# BrazoRobotico.net
KiCad netlist of a schematic drawn in EAGLE
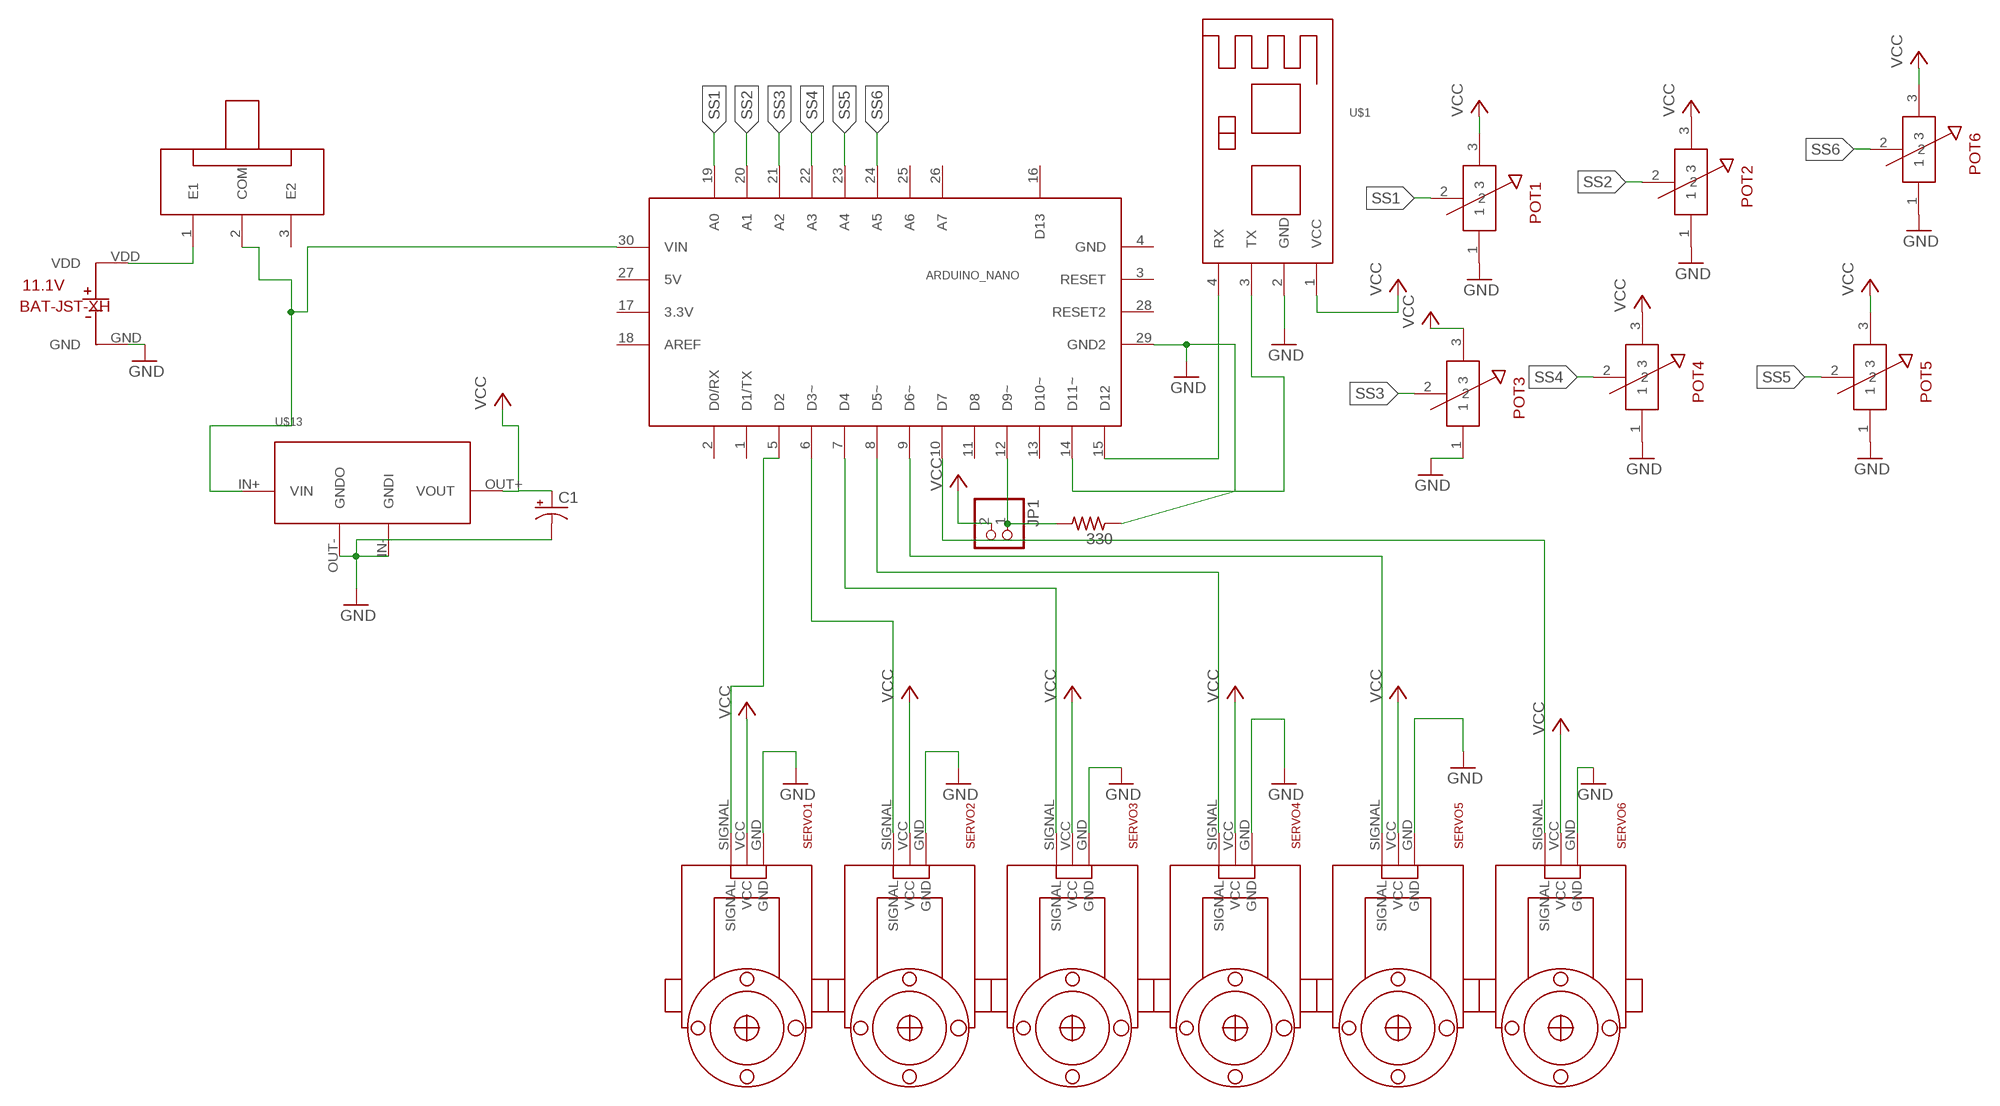
[diagram p0: schematic, sheet 1]

(export (version "E")
  (design (tool "Eeschema 10.0.6"))
  (components
    (comp (ref "11.1V")
      (value "BAT-JST-XH")
      (footprint "eagle-import:JST-XH-2")
      (libsource (lib "eagle-import") (part "BAT-JST-XH"))
    )
    (comp (ref "330")
      (value "R-US_0207/7")
      (footprint "eagle-import:0207_7")
      (libsource (lib "eagle-import") (part "R-US_0207/7"))
    )
    (comp (ref "ARDUINO_NANO")
      (value "NANO")
      (footprint "eagle-import:NANO")
      (libsource (lib "eagle-import") (part "NANO"))
    )
    (comp (ref "C1")
      (value "CPOL-USE5-10.5")
      (footprint "eagle-import:E5-10,5")
      (libsource (lib "eagle-import") (part "CPOL-USE5-10.5"))
    )
    (comp (ref "JP1")
      (value "PINHD-1X2")
      (footprint "eagle-import:1X02")
      (libsource (lib "eagle-import") (part "PINHD-1X2"))
    )
    (comp (ref "POT1")
      (value "POTENCIOMETRO_GDE")
      (footprint "eagle-import:POTENCIOMETRO_GENERICO")
      (libsource (lib "eagle-import") (part "POTENCIOMETRO_GDE"))
    )
    (comp (ref "POT2")
      (value "POTENCIOMETRO_GDE")
      (footprint "eagle-import:POTENCIOMETRO_GENERICO")
      (libsource (lib "eagle-import") (part "POTENCIOMETRO_GDE"))
    )
    (comp (ref "POT3")
      (value "POTENCIOMETRO_GDE")
      (footprint "eagle-import:POTENCIOMETRO_GENERICO")
      (libsource (lib "eagle-import") (part "POTENCIOMETRO_GDE"))
    )
    (comp (ref "POT4")
      (value "POTENCIOMETRO_GDE")
      (footprint "eagle-import:POTENCIOMETRO_GENERICO")
      (libsource (lib "eagle-import") (part "POTENCIOMETRO_GDE"))
    )
    (comp (ref "POT5")
      (value "POTENCIOMETRO_GDE")
      (footprint "eagle-import:POTENCIOMETRO_GENERICO")
      (libsource (lib "eagle-import") (part "POTENCIOMETRO_GDE"))
    )
    (comp (ref "POT6")
      (value "POTENCIOMETRO_GDE")
      (footprint "eagle-import:POTENCIOMETRO_GENERICO")
      (libsource (lib "eagle-import") (part "POTENCIOMETRO_GDE"))
    )
    (comp (ref "SERVO1")
      (value "SERVOMOTORES")
      (footprint "eagle-import:SERVO")
      (libsource (lib "eagle-import") (part "SERVOMOTORES"))
    )
    (comp (ref "SERVO2")
      (value "SERVOMOTORES")
      (footprint "eagle-import:SERVO")
      (libsource (lib "eagle-import") (part "SERVOMOTORES"))
    )
    (comp (ref "SERVO3")
      (value "SERVOMOTORES")
      (footprint "eagle-import:SERVO")
      (libsource (lib "eagle-import") (part "SERVOMOTORES"))
    )
    (comp (ref "SERVO4")
      (value "SERVOMOTORES")
      (footprint "eagle-import:SERVO")
      (libsource (lib "eagle-import") (part "SERVOMOTORES"))
    )
    (comp (ref "SERVO5")
      (value "SERVOMOTORES")
      (footprint "eagle-import:SERVO")
      (libsource (lib "eagle-import") (part "SERVOMOTORES"))
    )
    (comp (ref "SERVO6")
      (value "SERVOMOTORES")
      (footprint "eagle-import:SERVO")
      (libsource (lib "eagle-import") (part "SERVOMOTORES"))
    )
    (comp (ref "U$1")
      (value "HC-06")
      (footprint "eagle-import:HC-06")
      (libsource (lib "eagle-import") (part "HC-06"))
    )
    (comp (ref "U$13")
      (value "STEPDOWN")
      (footprint "eagle-import:STEPDOWN")
      (libsource (lib "eagle-import") (part "STEPDOWN"))
    )
    (comp (ref "U$14")
      (value "TRIPLEPOLO")
      (footprint "eagle-import:TRIPLEPOLO")
      (libsource (lib "eagle-import") (part "TRIPLEPOLO"))
    )
  )
  (nets
    (net (code "1") (name "GND") (class "Default")
      (node (ref "11.1V") (pin "GND") (pinfunction "GND_GND") (pintype "bidirectional"))
      (node (ref "330") (pin "1") (pinfunction "1_1") (pintype "passive"))
      (node (ref "ARDUINO_NANO") (pin "29") (pinfunction "GND2_29") (pintype "bidirectional"))
      (node (ref "C1") (pin "-") (pinfunction "-_-") (pintype "passive"))
      (node (ref "POT1") (pin "1") (pinfunction "1_1") (pintype "bidirectional"))
      (node (ref "POT2") (pin "1") (pinfunction "1_1") (pintype "bidirectional"))
      (node (ref "POT3") (pin "1") (pinfunction "1_1") (pintype "bidirectional"))
      (node (ref "POT4") (pin "1") (pinfunction "1_1") (pintype "bidirectional"))
      (node (ref "POT5") (pin "1") (pinfunction "1_1") (pintype "bidirectional"))
      (node (ref "POT6") (pin "1") (pinfunction "1_1") (pintype "bidirectional"))
      (node (ref "SERVO1") (pin "GND") (pinfunction "GND_GND") (pintype "bidirectional"))
      (node (ref "SERVO2") (pin "GND") (pinfunction "GND_GND") (pintype "bidirectional"))
      (node (ref "SERVO3") (pin "GND") (pinfunction "GND_GND") (pintype "bidirectional"))
      (node (ref "SERVO4") (pin "GND") (pinfunction "GND_GND") (pintype "bidirectional"))
      (node (ref "SERVO5") (pin "GND") (pinfunction "GND_GND") (pintype "bidirectional"))
      (node (ref "SERVO6") (pin "GND") (pinfunction "GND_GND") (pintype "bidirectional"))
      (node (ref "U$1") (pin "2") (pinfunction "GND_2") (pintype "bidirectional"))
      (node (ref "U$13") (pin "IN-") (pinfunction "GNDI_IN-") (pintype "bidirectional"))
      (node (ref "U$13") (pin "OUT-") (pinfunction "GNDO_OUT-") (pintype "bidirectional"))
    )
    (net (code "2") (name "Net-(ARDUINO_NANO-D2)") (class "Default")
      (node (ref "ARDUINO_NANO") (pin "5") (pinfunction "D2_5") (pintype "bidirectional"))
      (node (ref "SERVO1") (pin "SIGNAL") (pinfunction "SIGNAL_SIGNAL") (pintype "bidirectional"))
    )
    (net (code "3") (name "Net-(ARDUINO_NANO-D3~{})") (class "Default")
      (node (ref "ARDUINO_NANO") (pin "6") (pinfunction "D3~{}_6") (pintype "bidirectional"))
      (node (ref "SERVO2") (pin "SIGNAL") (pinfunction "SIGNAL_SIGNAL") (pintype "bidirectional"))
    )
    (net (code "4") (name "Net-(ARDUINO_NANO-D4)") (class "Default")
      (node (ref "ARDUINO_NANO") (pin "7") (pinfunction "D4_7") (pintype "bidirectional"))
      (node (ref "SERVO3") (pin "SIGNAL") (pinfunction "SIGNAL_SIGNAL") (pintype "bidirectional"))
    )
    (net (code "5") (name "Net-(ARDUINO_NANO-D5~{})") (class "Default")
      (node (ref "ARDUINO_NANO") (pin "8") (pinfunction "D5~{}_8") (pintype "bidirectional"))
      (node (ref "SERVO4") (pin "SIGNAL") (pinfunction "SIGNAL_SIGNAL") (pintype "bidirectional"))
    )
    (net (code "6") (name "Net-(ARDUINO_NANO-D6~{})") (class "Default")
      (node (ref "ARDUINO_NANO") (pin "9") (pinfunction "D6~{}_9") (pintype "bidirectional"))
      (node (ref "SERVO5") (pin "SIGNAL") (pinfunction "SIGNAL_SIGNAL") (pintype "bidirectional"))
    )
    (net (code "7") (name "Net-(ARDUINO_NANO-D7)") (class "Default")
      (node (ref "ARDUINO_NANO") (pin "10") (pinfunction "D7_10") (pintype "bidirectional"))
      (node (ref "SERVO6") (pin "SIGNAL") (pinfunction "SIGNAL_SIGNAL") (pintype "bidirectional"))
    )
    (net (code "8") (name "Net-(ARDUINO_NANO-D9~{})") (class "Default")
      (node (ref "330") (pin "2") (pinfunction "2_2") (pintype "passive"))
      (node (ref "ARDUINO_NANO") (pin "12") (pinfunction "D9~{}_12") (pintype "bidirectional"))
      (node (ref "JP1") (pin "1") (pinfunction "1_1") (pintype "passive"))
    )
    (net (code "9") (name "Net-(ARDUINO_NANO-D11~{})") (class "Default")
      (node (ref "ARDUINO_NANO") (pin "14") (pinfunction "D11~{}_14") (pintype "bidirectional"))
      (node (ref "U$1") (pin "3") (pinfunction "TX_3") (pintype "bidirectional"))
    )
    (net (code "10") (name "Net-(ARDUINO_NANO-D12)") (class "Default")
      (node (ref "ARDUINO_NANO") (pin "15") (pinfunction "D12_15") (pintype "bidirectional"))
      (node (ref "U$1") (pin "4") (pinfunction "RX_4") (pintype "bidirectional"))
    )
    (net (code "11") (name "Net-(ARDUINO_NANO-VIN)") (class "Default")
      (node (ref "ARDUINO_NANO") (pin "30") (pinfunction "VIN_30") (pintype "bidirectional"))
      (node (ref "U$13") (pin "IN+") (pinfunction "VIN_IN+") (pintype "bidirectional"))
      (node (ref "U$14") (pin "2") (pinfunction "COM_2") (pintype "bidirectional"))
    )
    (net (code "12") (name "Net-(U$14-E1)") (class "Default")
      (node (ref "11.1V") (pin "VDD") (pinfunction "VDD_VDD") (pintype "bidirectional"))
      (node (ref "U$14") (pin "1") (pinfunction "E1_1") (pintype "bidirectional"))
    )
    (net (code "13") (name "SS1") (class "Default")
      (node (ref "ARDUINO_NANO") (pin "19") (pinfunction "A0_19") (pintype "bidirectional"))
      (node (ref "POT1") (pin "2") (pinfunction "2_2") (pintype "bidirectional"))
    )
    (net (code "14") (name "SS2") (class "Default")
      (node (ref "ARDUINO_NANO") (pin "20") (pinfunction "A1_20") (pintype "bidirectional"))
      (node (ref "POT2") (pin "2") (pinfunction "2_2") (pintype "bidirectional"))
    )
    (net (code "15") (name "SS3") (class "Default")
      (node (ref "ARDUINO_NANO") (pin "21") (pinfunction "A2_21") (pintype "bidirectional"))
      (node (ref "POT3") (pin "2") (pinfunction "2_2") (pintype "bidirectional"))
    )
    (net (code "16") (name "SS4") (class "Default")
      (node (ref "ARDUINO_NANO") (pin "22") (pinfunction "A3_22") (pintype "bidirectional"))
      (node (ref "POT4") (pin "2") (pinfunction "2_2") (pintype "bidirectional"))
    )
    (net (code "17") (name "SS5") (class "Default")
      (node (ref "ARDUINO_NANO") (pin "23") (pinfunction "A4_23") (pintype "bidirectional"))
      (node (ref "POT5") (pin "2") (pinfunction "2_2") (pintype "bidirectional"))
    )
    (net (code "18") (name "SS6") (class "Default")
      (node (ref "ARDUINO_NANO") (pin "24") (pinfunction "A5_24") (pintype "bidirectional"))
      (node (ref "POT6") (pin "2") (pinfunction "2_2") (pintype "bidirectional"))
    )
    (net (code "19") (name "VCC") (class "Default")
      (node (ref "C1") (pin "+") (pinfunction "+_+") (pintype "passive"))
      (node (ref "JP1") (pin "2") (pinfunction "2_2") (pintype "passive"))
      (node (ref "POT1") (pin "3") (pinfunction "3_3") (pintype "bidirectional"))
      (node (ref "POT2") (pin "3") (pinfunction "3_3") (pintype "bidirectional"))
      (node (ref "POT3") (pin "3") (pinfunction "3_3") (pintype "bidirectional"))
      (node (ref "POT4") (pin "3") (pinfunction "3_3") (pintype "bidirectional"))
      (node (ref "POT5") (pin "3") (pinfunction "3_3") (pintype "bidirectional"))
      (node (ref "POT6") (pin "3") (pinfunction "3_3") (pintype "bidirectional"))
      (node (ref "SERVO1") (pin "VCC") (pinfunction "VCC_VCC") (pintype "bidirectional"))
      (node (ref "SERVO2") (pin "VCC") (pinfunction "VCC_VCC") (pintype "bidirectional"))
      (node (ref "SERVO3") (pin "VCC") (pinfunction "VCC_VCC") (pintype "bidirectional"))
      (node (ref "SERVO4") (pin "VCC") (pinfunction "VCC_VCC") (pintype "bidirectional"))
      (node (ref "SERVO5") (pin "VCC") (pinfunction "VCC_VCC") (pintype "bidirectional"))
      (node (ref "SERVO6") (pin "VCC") (pinfunction "VCC_VCC") (pintype "bidirectional"))
      (node (ref "U$1") (pin "1") (pinfunction "VCC_1") (pintype "bidirectional"))
      (node (ref "U$13") (pin "OUT+") (pinfunction "VOUT_OUT+") (pintype "bidirectional"))
    )
    (net (code "20") (name "unconnected-(ARDUINO_NANO-3.3V-Pad17)") (class "Default")
      (node (ref "ARDUINO_NANO") (pin "17") (pinfunction "3.3V_17") (pintype "bidirectional"))
    )
    (net (code "21") (name "unconnected-(ARDUINO_NANO-5V-Pad27)") (class "Default")
      (node (ref "ARDUINO_NANO") (pin "27") (pinfunction "5V_27") (pintype "bidirectional"))
    )
    (net (code "22") (name "unconnected-(ARDUINO_NANO-A6-Pad25)") (class "Default")
      (node (ref "ARDUINO_NANO") (pin "25") (pinfunction "A6_25") (pintype "bidirectional"))
    )
    (net (code "23") (name "unconnected-(ARDUINO_NANO-A7-Pad26)") (class "Default")
      (node (ref "ARDUINO_NANO") (pin "26") (pinfunction "A7_26") (pintype "bidirectional"))
    )
    (net (code "24") (name "unconnected-(ARDUINO_NANO-AREF-Pad18)") (class "Default")
      (node (ref "ARDUINO_NANO") (pin "18") (pinfunction "AREF_18") (pintype "bidirectional"))
    )
    (net (code "25") (name "unconnected-(ARDUINO_NANO-D0{slash}RX-Pad2)") (class "Default")
      (node (ref "ARDUINO_NANO") (pin "2") (pinfunction "D0/RX_2") (pintype "bidirectional"))
    )
    (net (code "26") (name "unconnected-(ARDUINO_NANO-D1{slash}TX-Pad1)") (class "Default")
      (node (ref "ARDUINO_NANO") (pin "1") (pinfunction "D1/TX_1") (pintype "bidirectional"))
    )
    (net (code "27") (name "unconnected-(ARDUINO_NANO-D8-Pad11)") (class "Default")
      (node (ref "ARDUINO_NANO") (pin "11") (pinfunction "D8_11") (pintype "bidirectional"))
    )
    (net (code "28") (name "unconnected-(ARDUINO_NANO-D10~{}-Pad13)") (class "Default")
      (node (ref "ARDUINO_NANO") (pin "13") (pinfunction "D10~{}_13") (pintype "bidirectional"))
    )
    (net (code "29") (name "unconnected-(ARDUINO_NANO-D13-Pad16)") (class "Default")
      (node (ref "ARDUINO_NANO") (pin "16") (pinfunction "D13_16") (pintype "bidirectional"))
    )
    (net (code "30") (name "unconnected-(ARDUINO_NANO-GND-Pad4)") (class "Default")
      (node (ref "ARDUINO_NANO") (pin "4") (pinfunction "GND_4") (pintype "bidirectional"))
    )
    (net (code "31") (name "unconnected-(ARDUINO_NANO-RESET-Pad3)") (class "Default")
      (node (ref "ARDUINO_NANO") (pin "3") (pinfunction "RESET_3") (pintype "bidirectional"))
    )
    (net (code "32") (name "unconnected-(ARDUINO_NANO-RESET2-Pad28)") (class "Default")
      (node (ref "ARDUINO_NANO") (pin "28") (pinfunction "RESET2_28") (pintype "bidirectional"))
    )
    (net (code "33") (name "unconnected-(U$14-E2-Pad3)") (class "Default")
      (node (ref "U$14") (pin "3") (pinfunction "E2_3") (pintype "bidirectional"))
    )
  )
)
